# IOB-I2C-MAX731x.net
KiCad netlist of a schematic drawn in EAGLE
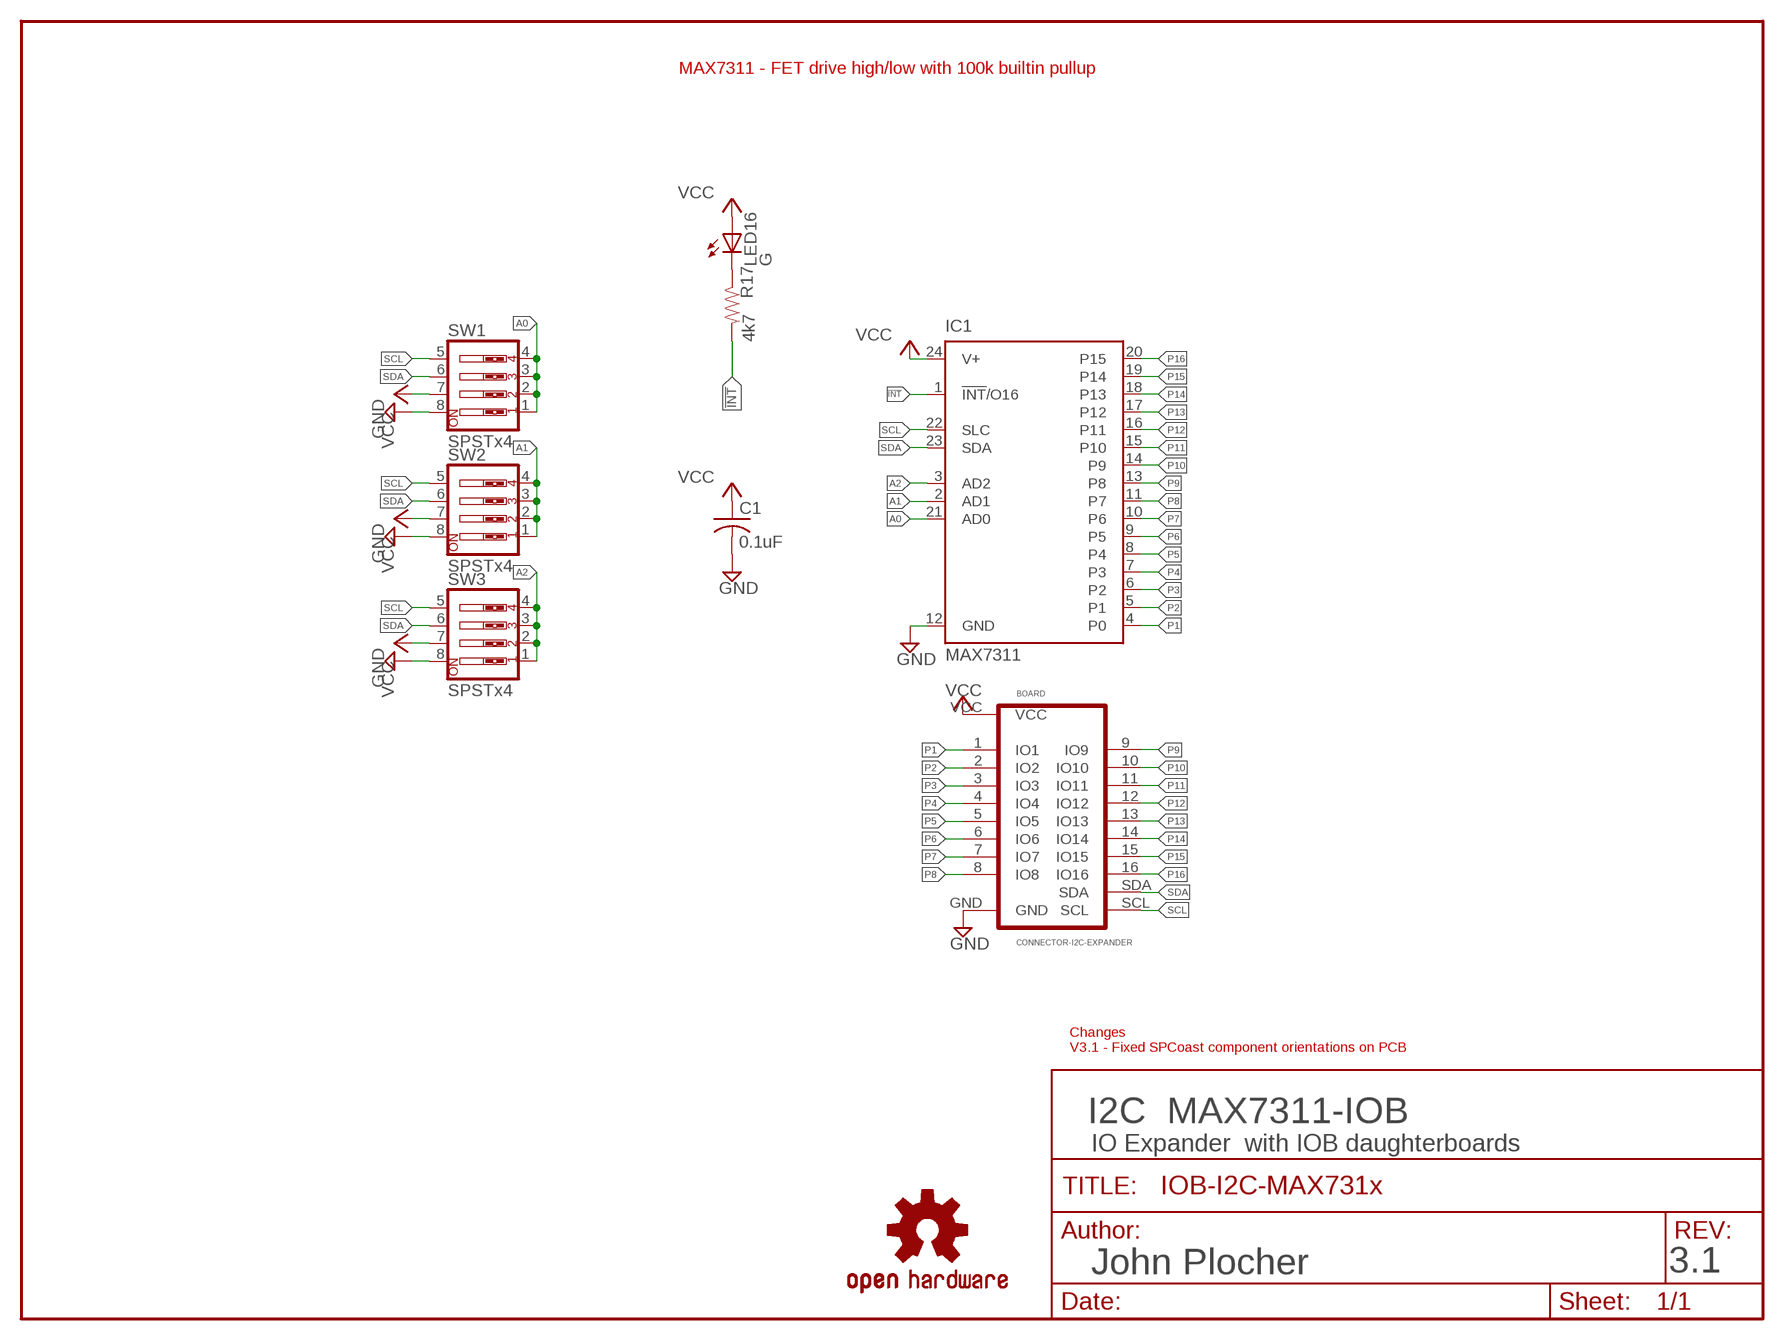
[diagram p0: schematic, sheet 1]

(export (version "E")
  (design (tool "Eeschema 10.0.6"))
  (components
    (comp (ref "BOARD")
      (value "CONNECTOR-I2C-EXPANDER")
      (footprint "eagle-import:I2C-EXPANDER")
      (libsource (lib "eagle-import") (part "CONNECTOR-I2C-EXPANDER"))
    )
    (comp (ref "C1")
      (value "0.1uF")
      (footprint "eagle-import:0603-CAP")
      (libsource (lib "eagle-import") (part "CAP0603"))
    )
    (comp (ref "IC1")
      (value "MAX7311")
      (footprint "eagle-import:TSSOP24")
      (libsource (lib "eagle-import") (part "MAX73XX/AUG"))
    )
    (comp (ref "LED16")
      (value "G")
      (footprint "eagle-import:0603-LED")
      (libsource (lib "eagle-import") (part "LED0603-LED"))
    )
    (comp (ref "R17")
      (value "4k7")
      (footprint "eagle-import:0603-RES")
      (libsource (lib "eagle-import") (part "R0603-RES"))
    )
    (comp (ref "SW1")
      (value "SPSTx4")
      (footprint "eagle-import:EDG-04")
      (libsource (lib "eagle-import") (part "SW_DIP-4"))
    )
    (comp (ref "SW2")
      (value "SPSTx4")
      (footprint "eagle-import:EDG-04")
      (libsource (lib "eagle-import") (part "SW_DIP-4"))
    )
    (comp (ref "SW3")
      (value "SPSTx4")
      (footprint "eagle-import:EDG-04")
      (libsource (lib "eagle-import") (part "SW_DIP-4"))
    )
    (comp (ref "U$1")
      (value "OSHW")
      (footprint "eagle-import:OSHW-LOGO-L")
      (libsource (lib "eagle-import") (part "DOC-OSHW-LOGO-L"))
    )
  )
  (nets
    (net (code "1") (name "/~{INT}") (class "Default")
      (node (ref "IC1") (pin "1") (pinfunction "~{INT}/O16_1") (pintype "open_collector"))
      (node (ref "R17") (pin "2") (pinfunction "2_2") (pintype "passive"))
    )
    (net (code "2") (name "A0") (class "Default")
      (node (ref "IC1") (pin "21") (pinfunction "AD0_21") (pintype "input"))
      (node (ref "SW1") (pin "1") (pinfunction "1_1") (pintype "passive"))
      (node (ref "SW1") (pin "2") (pinfunction "2_2") (pintype "passive"))
      (node (ref "SW1") (pin "3") (pinfunction "3_3") (pintype "passive"))
      (node (ref "SW1") (pin "4") (pinfunction "4_4") (pintype "passive"))
    )
    (net (code "3") (name "A1") (class "Default")
      (node (ref "IC1") (pin "2") (pinfunction "AD1_2") (pintype "input"))
      (node (ref "SW2") (pin "1") (pinfunction "1_1") (pintype "passive"))
      (node (ref "SW2") (pin "2") (pinfunction "2_2") (pintype "passive"))
      (node (ref "SW2") (pin "3") (pinfunction "3_3") (pintype "passive"))
      (node (ref "SW2") (pin "4") (pinfunction "4_4") (pintype "passive"))
    )
    (net (code "4") (name "A2") (class "Default")
      (node (ref "IC1") (pin "3") (pinfunction "AD2_3") (pintype "input"))
      (node (ref "SW3") (pin "1") (pinfunction "1_1") (pintype "passive"))
      (node (ref "SW3") (pin "2") (pinfunction "2_2") (pintype "passive"))
      (node (ref "SW3") (pin "3") (pinfunction "3_3") (pintype "passive"))
      (node (ref "SW3") (pin "4") (pinfunction "4_4") (pintype "passive"))
    )
    (net (code "5") (name "GND") (class "Default")
      (node (ref "BOARD") (pin "GND") (pinfunction "GND_GND") (pintype "bidirectional"))
      (node (ref "C1") (pin "2") (pinfunction "2_2") (pintype "passive"))
      (node (ref "IC1") (pin "12") (pinfunction "GND_12") (pintype "power_in"))
      (node (ref "SW1") (pin "8") (pinfunction "8_8") (pintype "passive"))
      (node (ref "SW2") (pin "8") (pinfunction "8_8") (pintype "passive"))
      (node (ref "SW3") (pin "8") (pinfunction "8_8") (pintype "passive"))
    )
    (net (code "6") (name "Net-(LED16-PadC)") (class "Default")
      (node (ref "LED16") (pin "C") (pinfunction "C_C") (pintype "passive"))
      (node (ref "R17") (pin "1") (pinfunction "1_1") (pintype "passive"))
    )
    (net (code "7") (name "P1") (class "Default")
      (node (ref "BOARD") (pin "1") (pinfunction "IO1_1") (pintype "bidirectional"))
      (node (ref "IC1") (pin "4") (pinfunction "P0_4") (pintype "bidirectional"))
    )
    (net (code "8") (name "P2") (class "Default")
      (node (ref "BOARD") (pin "2") (pinfunction "IO2_2") (pintype "bidirectional"))
      (node (ref "IC1") (pin "5") (pinfunction "P1_5") (pintype "bidirectional"))
    )
    (net (code "9") (name "P3") (class "Default")
      (node (ref "BOARD") (pin "3") (pinfunction "IO3_3") (pintype "bidirectional"))
      (node (ref "IC1") (pin "6") (pinfunction "P2_6") (pintype "bidirectional"))
    )
    (net (code "10") (name "P4") (class "Default")
      (node (ref "BOARD") (pin "4") (pinfunction "IO4_4") (pintype "bidirectional"))
      (node (ref "IC1") (pin "7") (pinfunction "P3_7") (pintype "bidirectional"))
    )
    (net (code "11") (name "P5") (class "Default")
      (node (ref "BOARD") (pin "5") (pinfunction "IO5_5") (pintype "bidirectional"))
      (node (ref "IC1") (pin "8") (pinfunction "P4_8") (pintype "bidirectional"))
    )
    (net (code "12") (name "P6") (class "Default")
      (node (ref "BOARD") (pin "6") (pinfunction "IO6_6") (pintype "bidirectional"))
      (node (ref "IC1") (pin "9") (pinfunction "P5_9") (pintype "bidirectional"))
    )
    (net (code "13") (name "P7") (class "Default")
      (node (ref "BOARD") (pin "7") (pinfunction "IO7_7") (pintype "bidirectional"))
      (node (ref "IC1") (pin "10") (pinfunction "P6_10") (pintype "bidirectional"))
    )
    (net (code "14") (name "P8") (class "Default")
      (node (ref "BOARD") (pin "8") (pinfunction "IO8_8") (pintype "bidirectional"))
      (node (ref "IC1") (pin "11") (pinfunction "P7_11") (pintype "bidirectional"))
    )
    (net (code "15") (name "P9") (class "Default")
      (node (ref "BOARD") (pin "9") (pinfunction "IO9_9") (pintype "bidirectional"))
      (node (ref "IC1") (pin "13") (pinfunction "P8_13") (pintype "bidirectional"))
    )
    (net (code "16") (name "P10") (class "Default")
      (node (ref "BOARD") (pin "10") (pinfunction "IO10_10") (pintype "bidirectional"))
      (node (ref "IC1") (pin "14") (pinfunction "P9_14") (pintype "bidirectional"))
    )
    (net (code "17") (name "P11") (class "Default")
      (node (ref "BOARD") (pin "11") (pinfunction "IO11_11") (pintype "bidirectional"))
      (node (ref "IC1") (pin "15") (pinfunction "P10_15") (pintype "bidirectional"))
    )
    (net (code "18") (name "P12") (class "Default")
      (node (ref "BOARD") (pin "12") (pinfunction "IO12_12") (pintype "bidirectional"))
      (node (ref "IC1") (pin "16") (pinfunction "P11_16") (pintype "bidirectional"))
    )
    (net (code "19") (name "P13") (class "Default")
      (node (ref "BOARD") (pin "13") (pinfunction "IO13_13") (pintype "bidirectional"))
      (node (ref "IC1") (pin "17") (pinfunction "P12_17") (pintype "bidirectional"))
    )
    (net (code "20") (name "P14") (class "Default")
      (node (ref "BOARD") (pin "14") (pinfunction "IO14_14") (pintype "bidirectional"))
      (node (ref "IC1") (pin "18") (pinfunction "P13_18") (pintype "bidirectional"))
    )
    (net (code "21") (name "P15") (class "Default")
      (node (ref "BOARD") (pin "15") (pinfunction "IO15_15") (pintype "bidirectional"))
      (node (ref "IC1") (pin "19") (pinfunction "P14_19") (pintype "bidirectional"))
    )
    (net (code "22") (name "P16") (class "Default")
      (node (ref "BOARD") (pin "16") (pinfunction "IO16_16") (pintype "bidirectional"))
      (node (ref "IC1") (pin "20") (pinfunction "P15_20") (pintype "bidirectional"))
    )
    (net (code "23") (name "SCL") (class "Default")
      (node (ref "BOARD") (pin "SCL") (pinfunction "SCL_SCL") (pintype "bidirectional"))
      (node (ref "IC1") (pin "22") (pinfunction "SLC_22") (pintype "input"))
      (node (ref "SW1") (pin "5") (pinfunction "5_5") (pintype "passive"))
      (node (ref "SW2") (pin "5") (pinfunction "5_5") (pintype "passive"))
      (node (ref "SW3") (pin "5") (pinfunction "5_5") (pintype "passive"))
    )
    (net (code "24") (name "SDA") (class "Default")
      (node (ref "BOARD") (pin "SDA") (pinfunction "SDA_SDA") (pintype "bidirectional"))
      (node (ref "IC1") (pin "23") (pinfunction "SDA_23") (pintype "bidirectional"))
      (node (ref "SW1") (pin "6") (pinfunction "6_6") (pintype "passive"))
      (node (ref "SW2") (pin "6") (pinfunction "6_6") (pintype "passive"))
      (node (ref "SW3") (pin "6") (pinfunction "6_6") (pintype "passive"))
    )
    (net (code "25") (name "VCC") (class "Default")
      (node (ref "BOARD") (pin "VCC") (pinfunction "VCC_VCC") (pintype "bidirectional"))
      (node (ref "C1") (pin "1") (pinfunction "1_1") (pintype "passive"))
      (node (ref "IC1") (pin "24") (pinfunction "V+_24") (pintype "power_in"))
      (node (ref "LED16") (pin "A") (pinfunction "A_A") (pintype "passive"))
      (node (ref "SW1") (pin "7") (pinfunction "7_7") (pintype "passive"))
      (node (ref "SW2") (pin "7") (pinfunction "7_7") (pintype "passive"))
      (node (ref "SW3") (pin "7") (pinfunction "7_7") (pintype "passive"))
    )
  )
)
